# Spindle_Control.net
KiCad netlist of a schematic drawn in Altium Designer
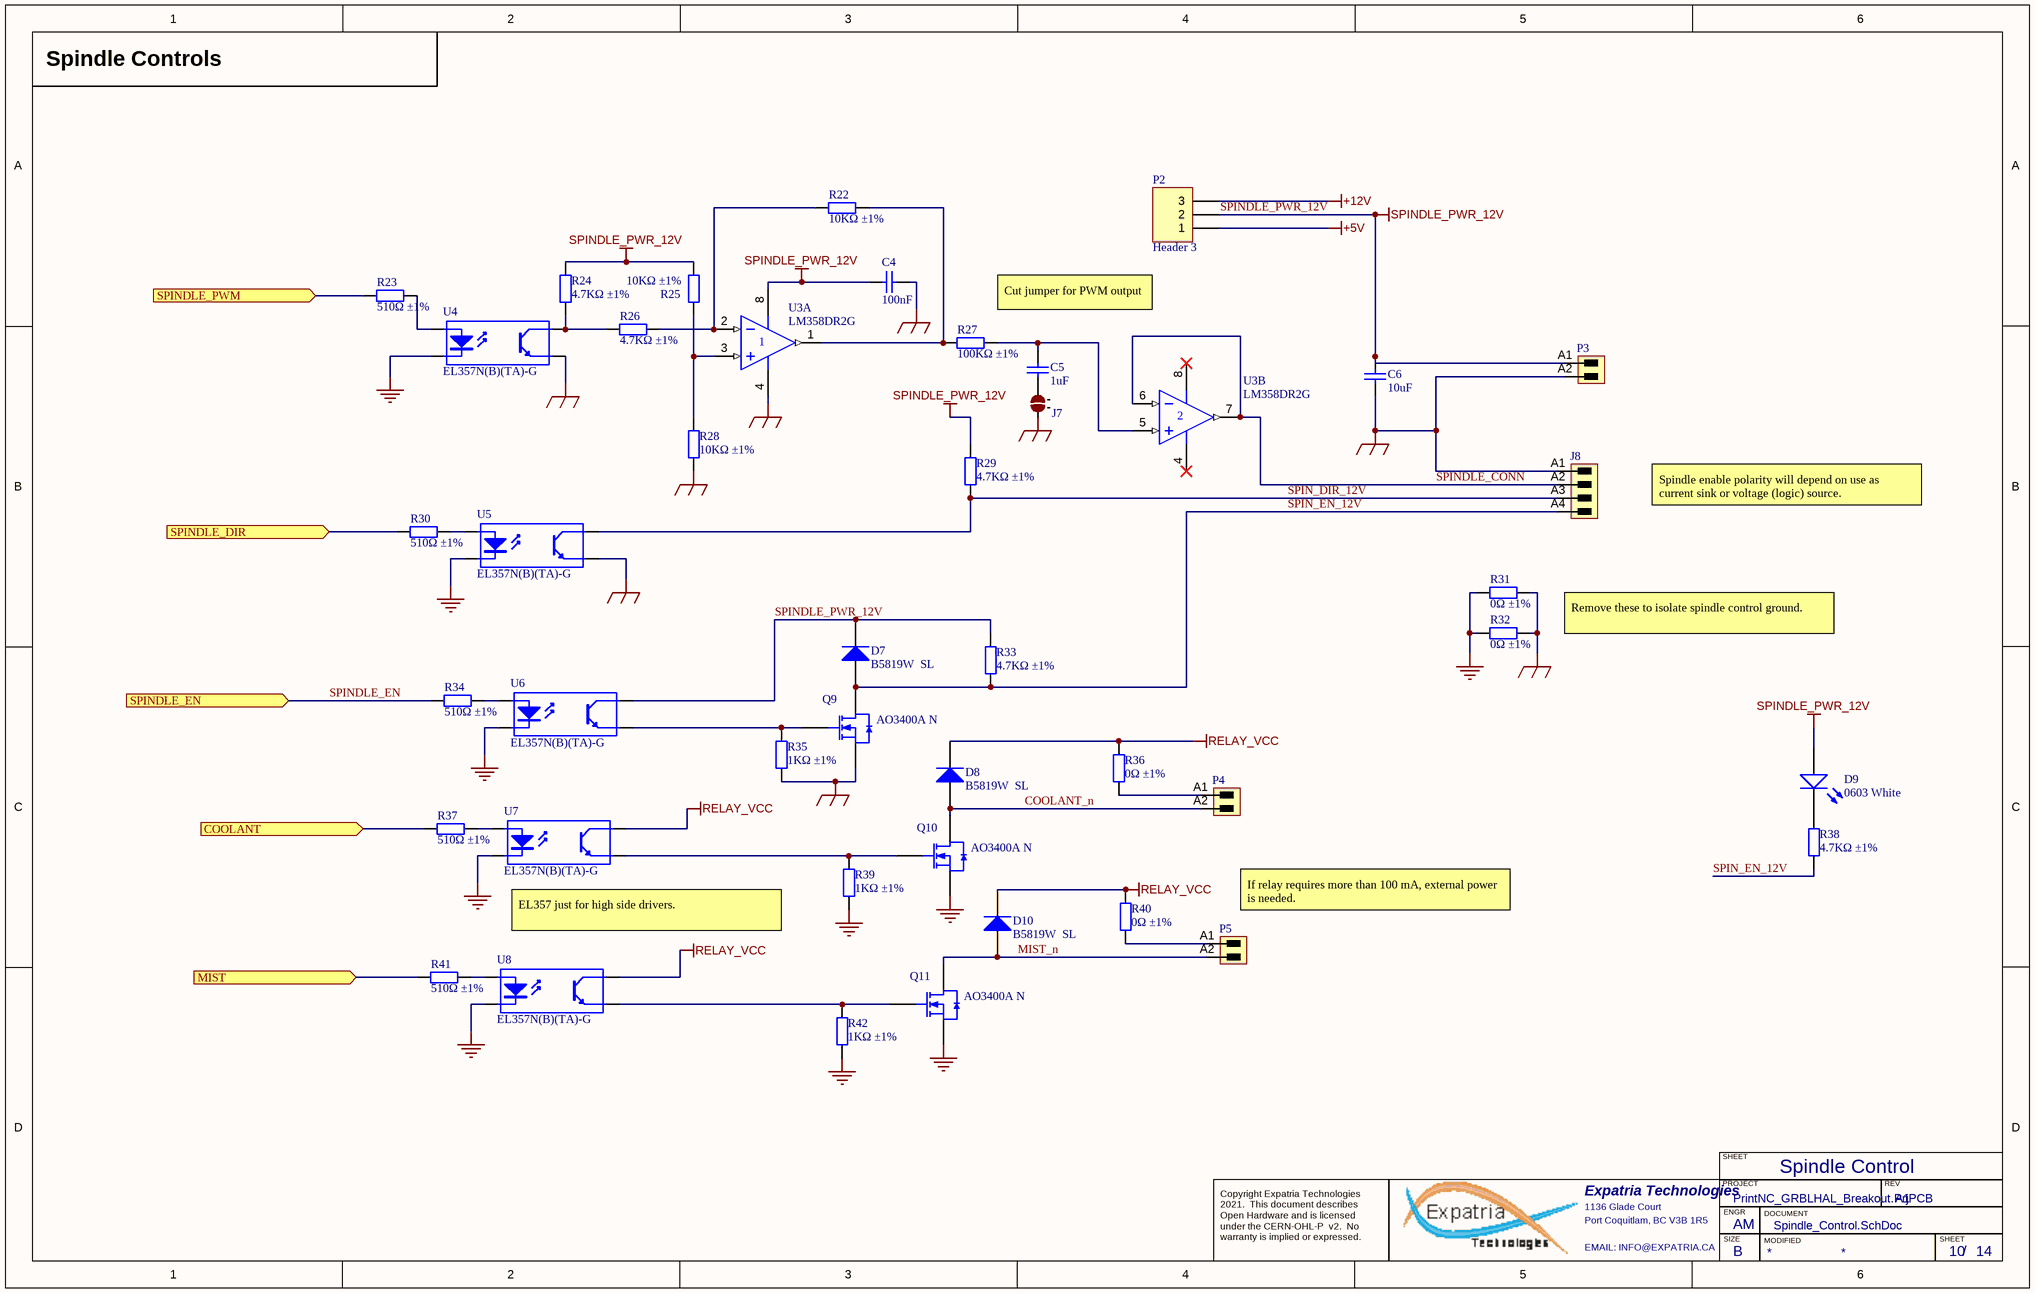
[diagram p0: Spindle_Control.SchDoc]

(export (version "E")
  (design (tool "Eeschema 10.0.6"))
  (components
    (comp (ref "C4")
      (value "100nF")
      (footprint "0603_C")
      (description "Chip capacitors")
      (fields (field (name "MANUFACTURER") "YAGEO") (field (name "PARTNUMBER") "CC0603KRX7R9BB104"))
      (libsource (lib "Cap") (part "0603 100nF (104) 10% 50V"))
    )
    (comp (ref "C5")
      (value "1uF")
      (footprint "0603_C")
      (description "Chip capacitors")
      (fields
        (field (name "MANUFACTURER") "Samsung Electro-Mechanics")
        (field (name "PARTNUMBER") "CL10A105KB8NNNC")
      )
      (libsource (lib "Cap") (part "0603 1uF (105) 10% 50V"))
    )
    (comp (ref "C6")
      (value "10uF")
      (footprint "1206_C")
      (description "Chip capacitors")
      (fields
        (field (name "MANUFACTURER") "Samsung Electro-Mechanics")
        (field (name "PARTNUMBER") "CL31A106KBHNNNE")
      )
      (libsource (lib "Cap") (part "1206 10uF (106) 10% 50V"))
    )
    (comp (ref "D7")
      (value "B5819W  SL")
      (footprint "SOD-123")
      (description "Schottky Diode")
      (libsource (lib "Diode") (part "SOD-123 B5819W  SL"))
    )
    (comp (ref "D8")
      (value "B5819W  SL")
      (footprint "SOD-123")
      (description "Schottky Diode")
      (libsource (lib "Diode") (part "SOD-123 B5819W  SL"))
    )
    (comp (ref "D9")
      (value "0603 White")
      (footprint "0603_LED_S1")
      (description "LED")
      (libsource (lib "LED") (part "0603 LED White"))
    )
    (comp (ref "D10")
      (value "B5819W  SL")
      (footprint "SOD-123")
      (description "Schottky Diode")
      (libsource (lib "Diode") (part "SOD-123 B5819W  SL"))
    )
    (comp (ref "J7")
      (value "2 way net solder junction - Normally Open")
      (footprint "2waySolder_NO")
      (libsource (lib "NetTieLib") (part "2waySolderNO"))
    )
    (comp (ref "J8")
      (value "~")
      (footprint "SL_SMT_3_5_180G_04")
      (description "OMNIMATE Signal - series BL/SL 3.50")
      (fields (field (name "PARTNUMBER") "1751264") (field (name "MANUFACTURER") "Phoenix Contact"))
      (libsource (lib "PrintNC_GRBLHAL_Breakout") (part "Header_Male_04_1x04"))
    )
    (comp (ref "P2")
      (value "Header 3")
      (footprint "HDR1X3")
      (description "Header, 3-Pin")
      (fields (field (name "PUBLISHER") "Altium Limited"))
      (libsource (lib "PrintNC_GRBLHAL_Breakout") (part "Header 3"))
    )
    (comp (ref "P3")
      (value "~")
      (footprint "SL_3_50_180G_02")
      (fields
        (field (name "PARTNUMBER") "WJ15EDGVC-3.5-2P")
        (field (name "MANUFACTURER") "Ningbo Kangnex Elec")
      )
      (libsource (lib "PrintNC_GRBLHAL_Breakout") (part "Header_Male_02_1x02"))
    )
    (comp (ref "P4")
      (value "~")
      (footprint "SL_3_50_180G_02")
      (fields
        (field (name "PARTNUMBER") "WJ15EDGVC-3.5-2P")
        (field (name "MANUFACTURER") "Ningbo Kangnex Elec")
      )
      (libsource (lib "PrintNC_GRBLHAL_Breakout") (part "Header_Male_02_1x02"))
    )
    (comp (ref "P5")
      (value "~")
      (footprint "SL_3_50_180G_02")
      (fields
        (field (name "PARTNUMBER") "WJ15EDGVC-3.5-2P")
        (field (name "MANUFACTURER") "Ningbo Kangnex Elec")
      )
      (libsource (lib "PrintNC_GRBLHAL_Breakout") (part "Header_Male_02_1x02"))
    )
    (comp (ref "Q9")
      (value "AO3400A N")
      (footprint "SOT-23-3L")
      (description "MOS(场效应管)")
      (libsource (lib "PrintNC_GRBLHAL_Breakout") (part "AO3400A N道沟 X0YV1T SOT-23"))
    )
    (comp (ref "Q10")
      (value "AO3400A N")
      (footprint "SOT-23-3L")
      (description "MOS(场效应管)")
      (libsource (lib "PrintNC_GRBLHAL_Breakout") (part "AO3400A N道沟 X0YV1T SOT-23"))
    )
    (comp (ref "Q11")
      (value "AO3400A N")
      (footprint "SOT-23-3L")
      (description "MOS(场效应管)")
      (libsource (lib "PrintNC_GRBLHAL_Breakout") (part "AO3400A N道沟 X0YV1T SOT-23"))
    )
    (comp (ref "R22")
      (value "10KΩ ±1%")
      (footprint "0402_R")
      (description "Chip resistor")
      (fields (field (name "MANUFACTURER") "Uniroyal Elec") (field (name "PARTNUMBER") "0402WGF1002TCE"))
      (libsource (lib "") (part "0402 10K (1002) 1%_1"))
    )
    (comp (ref "R23")
      (value "510Ω ±1%")
      (footprint "0402_R")
      (description "Chip resistor")
      (fields (field (name "MANUFACTURER") "Uniroyal Elec") (field (name "PARTNUMBER") "0402WGF5100TCE"))
      (libsource (lib "PrintNC_GRBLHAL_Breakout") (part "0402 510R (5100) 1%"))
    )
    (comp (ref "R24")
      (value "4.7KΩ ±1%")
      (footprint "0402_R")
      (description "Chip resistor")
      (fields (field (name "MANUFACTURER") "Uniroyal Elec") (field (name "PARTNUMBER") "0402WGF4701TCE"))
      (libsource (lib "") (part "0402 4.7K (4701) 1%_2"))
    )
    (comp (ref "R25")
      (value "10KΩ ±1%")
      (footprint "0402_R")
      (description "Chip resistor")
      (fields (field (name "MANUFACTURER") "Uniroyal Elec") (field (name "PARTNUMBER") "0402WGF1002TCE"))
      (libsource (lib "PrintNC_GRBLHAL_Breakout") (part "0402 10K (1002) 1%"))
    )
    (comp (ref "R26")
      (value "4.7KΩ ±1%")
      (footprint "0402_R")
      (description "Chip resistor")
      (fields (field (name "MANUFACTURER") "Uniroyal Elec") (field (name "PARTNUMBER") "0402WGF4701TCE"))
      (libsource (lib "") (part "0402 4.7K (4701) 1%_1"))
    )
    (comp (ref "R27")
      (value "100KΩ ±1%")
      (footprint "0402_R")
      (description "Chip resistor")
      (fields (field (name "MANUFACTURER") "Uniroyal Elec") (field (name "PARTNUMBER") "0402WGF1003TCE"))
      (libsource (lib "PrintNC_GRBLHAL_Breakout") (part "0402 100K (1003) 1%"))
    )
    (comp (ref "R28")
      (value "10KΩ ±1%")
      (footprint "0402_R")
      (description "Chip resistor")
      (fields (field (name "MANUFACTURER") "Uniroyal Elec") (field (name "PARTNUMBER") "0402WGF1002TCE"))
      (libsource (lib "PrintNC_GRBLHAL_Breakout") (part "0402 10K (1002) 1%"))
    )
    (comp (ref "R29")
      (value "4.7KΩ ±1%")
      (footprint "0402_R")
      (description "Chip resistor")
      (fields (field (name "MANUFACTURER") "Uniroyal Elec") (field (name "PARTNUMBER") "0402WGF4701TCE"))
      (libsource (lib "PrintNC_GRBLHAL_Breakout") (part "0402 4.7K (4701) 1%"))
    )
    (comp (ref "R30")
      (value "510Ω ±1%")
      (footprint "0402_R")
      (description "Chip resistor")
      (fields (field (name "MANUFACTURER") "Uniroyal Elec") (field (name "PARTNUMBER") "0402WGF5100TCE"))
      (libsource (lib "PrintNC_GRBLHAL_Breakout") (part "0402 510R (5100) 1%"))
    )
    (comp (ref "R31")
      (value "0Ω ±1%")
      (footprint "0402_R")
      (description "Chip resistor")
      (fields (field (name "POWER") "1/16W") (field (name "MANUFACTURER") "Uniroyal Elec"))
      (libsource (lib "PrintNC_GRBLHAL_Breakout") (part "0402 0R (0R0) 1%"))
    )
    (comp (ref "R32")
      (value "0Ω ±1%")
      (footprint "0402_R")
      (description "Chip resistor")
      (fields (field (name "POWER") "1/16W") (field (name "MANUFACTURER") "Uniroyal Elec"))
      (libsource (lib "PrintNC_GRBLHAL_Breakout") (part "0402 0R (0R0) 1%"))
    )
    (comp (ref "R33")
      (value "4.7KΩ ±1%")
      (footprint "0402_R")
      (description "Chip resistor")
      (fields (field (name "MANUFACTURER") "Uniroyal Elec") (field (name "PARTNUMBER") "0402WGF4701TCE"))
      (libsource (lib "PrintNC_GRBLHAL_Breakout") (part "0402 4.7K (4701) 1%"))
    )
    (comp (ref "R34")
      (value "510Ω ±1%")
      (footprint "0402_R")
      (description "Chip resistor")
      (fields (field (name "MANUFACTURER") "Uniroyal Elec") (field (name "PARTNUMBER") "0402WGF5100TCE"))
      (libsource (lib "PrintNC_GRBLHAL_Breakout") (part "0402 510R (5100) 1%"))
    )
    (comp (ref "R35")
      (value "1KΩ ±1%")
      (footprint "0402_R")
      (description "Chip resistor")
      (fields (field (name "MANUFACTURER") "Uniroyal Elec") (field (name "PARTNUMBER") "0402WGF1001TCE"))
      (libsource (lib "") (part "0402 1K (1001) 1%_1"))
    )
    (comp (ref "R36")
      (value "0Ω ±1%")
      (footprint "0402_R")
      (description "Chip resistor")
      (fields (field (name "MANUFACTURER") "Uniroyal Elec") (field (name "PARTNUMBER") "0402WGF0000TCE"))
      (libsource (lib "") (part "0402 0R (0R0) 1%_1"))
    )
    (comp (ref "R37")
      (value "510Ω ±1%")
      (footprint "0402_R")
      (description "Chip resistor")
      (fields (field (name "MANUFACTURER") "Uniroyal Elec") (field (name "PARTNUMBER") "0402WGF5100TCE"))
      (libsource (lib "PrintNC_GRBLHAL_Breakout") (part "0402 510R (5100) 1%"))
    )
    (comp (ref "R38")
      (value "4.7KΩ ±1%")
      (footprint "0402_R")
      (description "Chip resistor")
      (fields (field (name "MANUFACTURER") "Uniroyal Elec") (field (name "PARTNUMBER") "0402WGF4701TCE"))
      (libsource (lib "PrintNC_GRBLHAL_Breakout") (part "0402 4.7K (4701) 1%"))
    )
    (comp (ref "R39")
      (value "1KΩ ±1%")
      (footprint "0402_R")
      (description "Chip resistor")
      (fields (field (name "MANUFACTURER") "Uniroyal Elec") (field (name "PARTNUMBER") "0402WGF1001TCE"))
      (libsource (lib "PrintNC_GRBLHAL_Breakout") (part "0402 1K (1001) 1%"))
    )
    (comp (ref "R40")
      (value "0Ω ±1%")
      (footprint "0402_R")
      (description "Chip resistor")
      (fields (field (name "MANUFACTURER") "Uniroyal Elec") (field (name "PARTNUMBER") "0402WGF0000TCE"))
      (libsource (lib "") (part "0402 0R (0R0) 1%_1"))
    )
    (comp (ref "R41")
      (value "510Ω ±1%")
      (footprint "0402_R")
      (description "Chip resistor")
      (fields (field (name "MANUFACTURER") "Uniroyal Elec") (field (name "PARTNUMBER") "0402WGF5100TCE"))
      (libsource (lib "PrintNC_GRBLHAL_Breakout") (part "0402 510R (5100) 1%"))
    )
    (comp (ref "R42")
      (value "1KΩ ±1%")
      (footprint "0402_R")
      (description "Chip resistor")
      (fields (field (name "MANUFACTURER") "Uniroyal Elec") (field (name "PARTNUMBER") "0402WGF1001TCE"))
      (libsource (lib "PrintNC_GRBLHAL_Breakout") (part "0402 1K (1001) 1%"))
    )
    (comp (ref "U3")
      (value "LM358DR2G")
      (footprint "SOIC-8_150mil")
      (description "LM358DR2G,  Dual Op Amp,  5 - 28 V,  8-PinSOIC")
      (libsource (lib "PrintNC_GRBLHAL_Breakout") (part "LM358DR2G_[C7950]"))
    )
    (comp (ref "U4")
      (value "EL357N(B)(TA)-G")
      (footprint "SOP-4_P2.54")
      (description "Optocoupler SOP-4, EL357N(B)(TA)-G, Everlight Electronics")
      (libsource (lib "PrintNC_GRBLHAL_Breakout") (part "EL357N(B)(TA)-G_[C6649]"))
    )
    (comp (ref "U5")
      (value "EL357N(B)(TA)-G")
      (footprint "SOP-4_P2.54")
      (description "Optocoupler SOP-4, EL357N(B)(TA)-G, Everlight Electronics")
      (libsource (lib "PrintNC_GRBLHAL_Breakout") (part "EL357N(B)(TA)-G_[C6649]"))
    )
    (comp (ref "U6")
      (value "EL357N(B)(TA)-G")
      (footprint "SOP-4_P2.54")
      (description "Optocoupler SOP-4, EL357N(B)(TA)-G, Everlight Electronics")
      (libsource (lib "PrintNC_GRBLHAL_Breakout") (part "EL357N(B)(TA)-G_[C6649]"))
    )
    (comp (ref "U7")
      (value "EL357N(B)(TA)-G")
      (footprint "SOP-4_P2.54")
      (description "Optocoupler SOP-4, EL357N(B)(TA)-G, Everlight Electronics")
      (libsource (lib "PrintNC_GRBLHAL_Breakout") (part "EL357N(B)(TA)-G_[C6649]"))
    )
    (comp (ref "U8")
      (value "EL357N(B)(TA)-G")
      (footprint "SOP-4_P2.54")
      (description "Optocoupler SOP-4, EL357N(B)(TA)-G, Everlight Electronics")
      (libsource (lib "PrintNC_GRBLHAL_Breakout") (part "EL357N(B)(TA)-G_[C6649]"))
    )
  )
  (nets
    (net (code "1") (name "+5V") (class "Default")
      (node (ref "P2") (pin "1") (pinfunction "1_1") (pintype "passive"))
    )
    (net (code "2") (name "+12V") (class "Default")
      (node (ref "P2") (pin "3") (pinfunction "3_3") (pintype "passive"))
    )
    (net (code "3") (name "/COOLANT") (class "Default")
      (node (ref "R37") (pin "1") (pinfunction "1_1") (pintype "passive"))
    )
    (net (code "4") (name "/COOLANT_n") (class "Default")
      (node (ref "D8") (pin "1") (pinfunction "A_1") (pintype "passive"))
      (node (ref "P4") (pin "A2") (pinfunction "A2_A2") (pintype "passive"))
      (node (ref "Q10") (pin "3") (pinfunction "D_3") (pintype "passive"))
    )
    (net (code "5") (name "/MIST") (class "Default")
      (node (ref "R41") (pin "1") (pinfunction "1_1") (pintype "passive"))
    )
    (net (code "6") (name "/MIST_n") (class "Default")
      (node (ref "D10") (pin "1") (pinfunction "A_1") (pintype "passive"))
      (node (ref "P5") (pin "A2") (pinfunction "A2_A2") (pintype "passive"))
      (node (ref "Q11") (pin "3") (pinfunction "D_3") (pintype "passive"))
    )
    (net (code "7") (name "/SPINDLE_CONN") (class "Default")
      (node (ref "J8") (pin "A2") (pinfunction "A2_A2") (pintype "passive"))
      (node (ref "U3") (pin "6") (pinfunction "IN-_6") (pintype "input"))
      (node (ref "U3") (pin "7") (pinfunction "OUT_7") (pintype "output"))
    )
    (net (code "8") (name "/SPINDLE_DIR") (class "Default")
      (node (ref "R30") (pin "1") (pinfunction "1_1") (pintype "passive"))
    )
    (net (code "9") (name "/SPINDLE_EN") (class "Default")
      (node (ref "R34") (pin "1") (pinfunction "1_1") (pintype "passive"))
    )
    (net (code "10") (name "/SPINDLE_PWM") (class "Default")
      (node (ref "R23") (pin "1") (pinfunction "1_1") (pintype "passive"))
    )
    (net (code "11") (name "/SPIN_DIR_12V") (class "Default")
      (node (ref "J8") (pin "A3") (pinfunction "A3_A3") (pintype "passive"))
      (node (ref "R29") (pin "1") (pinfunction "1_1") (pintype "passive"))
      (node (ref "U5") (pin "4") (pinfunction "C_4") (pintype "passive"))
    )
    (net (code "12") (name "/SPIN_EN_12V") (class "Default")
      (node (ref "D7") (pin "1") (pinfunction "A_1") (pintype "passive"))
      (node (ref "J8") (pin "A4") (pinfunction "A4_A4") (pintype "passive"))
      (node (ref "Q9") (pin "3") (pinfunction "D_3") (pintype "passive"))
      (node (ref "R33") (pin "1") (pinfunction "1_1") (pintype "passive"))
      (node (ref "R38") (pin "1") (pinfunction "1_1") (pintype "passive"))
    )
    (net (code "13") (name "GND") (class "Default")
      (node (ref "Q10") (pin "2") (pinfunction "S_2") (pintype "passive"))
      (node (ref "Q11") (pin "2") (pinfunction "S_2") (pintype "passive"))
      (node (ref "R31") (pin "1") (pinfunction "1_1") (pintype "passive"))
      (node (ref "R32") (pin "1") (pinfunction "1_1") (pintype "passive"))
      (node (ref "R39") (pin "1") (pinfunction "1_1") (pintype "passive"))
      (node (ref "R42") (pin "1") (pinfunction "1_1") (pintype "passive"))
      (node (ref "U4") (pin "2") (pinfunction "K_2") (pintype "passive"))
      (node (ref "U5") (pin "2") (pinfunction "K_2") (pintype "passive"))
      (node (ref "U6") (pin "2") (pinfunction "K_2") (pintype "passive"))
      (node (ref "U7") (pin "2") (pinfunction "K_2") (pintype "passive"))
      (node (ref "U8") (pin "2") (pinfunction "K_2") (pintype "passive"))
    )
    (net (code "14") (name "Net-(C5-Pad1)") (class "Default")
      (node (ref "C5") (pin "1") (pinfunction "1_1") (pintype "passive"))
      (node (ref "J7") (pin "2") (pinfunction "2_2") (pintype "passive"))
    )
    (net (code "15") (name "Net-(D9-PadK)") (class "Default")
      (node (ref "D9") (pin "K") (pinfunction "K_K") (pintype "passive"))
      (node (ref "R38") (pin "2") (pinfunction "2_2") (pintype "passive"))
    )
    (net (code "16") (name "Net-(P4-PadA1)") (class "Default")
      (node (ref "P4") (pin "A1") (pinfunction "A1_A1") (pintype "passive"))
      (node (ref "R36") (pin "2") (pinfunction "2_2") (pintype "passive"))
    )
    (net (code "17") (name "Net-(P5-PadA1)") (class "Default")
      (node (ref "P5") (pin "A1") (pinfunction "A1_A1") (pintype "passive"))
      (node (ref "R40") (pin "2") (pinfunction "2_2") (pintype "passive"))
    )
    (net (code "18") (name "Net-(Q9-G)") (class "Default")
      (node (ref "Q9") (pin "1") (pinfunction "G_1") (pintype "passive"))
      (node (ref "R35") (pin "1") (pinfunction "1_1") (pintype "passive"))
      (node (ref "U6") (pin "3") (pinfunction "E_3") (pintype "passive"))
    )
    (net (code "19") (name "Net-(Q10-G)") (class "Default")
      (node (ref "Q10") (pin "1") (pinfunction "G_1") (pintype "passive"))
      (node (ref "R39") (pin "2") (pinfunction "2_2") (pintype "passive"))
      (node (ref "U7") (pin "3") (pinfunction "E_3") (pintype "passive"))
    )
    (net (code "20") (name "Net-(Q11-G)") (class "Default")
      (node (ref "Q11") (pin "1") (pinfunction "G_1") (pintype "passive"))
      (node (ref "R42") (pin "2") (pinfunction "2_2") (pintype "passive"))
      (node (ref "U8") (pin "3") (pinfunction "E_3") (pintype "passive"))
    )
    (net (code "21") (name "Net-(U3A-IN+)") (class "Default")
      (node (ref "R25") (pin "2") (pinfunction "2_2") (pintype "passive"))
      (node (ref "R28") (pin "1") (pinfunction "1_1") (pintype "passive"))
      (node (ref "U3") (pin "3") (pinfunction "IN+_3") (pintype "input"))
    )
    (net (code "22") (name "Net-(U3A-IN-)") (class "Default")
      (node (ref "R22") (pin "1") (pinfunction "1_1") (pintype "passive"))
      (node (ref "R26") (pin "2") (pinfunction "2_2") (pintype "passive"))
      (node (ref "U3") (pin "2") (pinfunction "IN-_2") (pintype "input"))
    )
    (net (code "23") (name "Net-(U3A-OUT)") (class "Default")
      (node (ref "R22") (pin "2") (pinfunction "2_2") (pintype "passive"))
      (node (ref "R27") (pin "2") (pinfunction "2_2") (pintype "passive"))
      (node (ref "U3") (pin "1") (pinfunction "OUT_1") (pintype "output"))
    )
    (net (code "24") (name "Net-(U3B-IN+)") (class "Default")
      (node (ref "C5") (pin "2") (pinfunction "2_2") (pintype "passive"))
      (node (ref "R27") (pin "1") (pinfunction "1_1") (pintype "passive"))
      (node (ref "U3") (pin "5") (pinfunction "IN+_5") (pintype "input"))
    )
    (net (code "25") (name "Net-(U4-A)") (class "Default")
      (node (ref "R23") (pin "2") (pinfunction "2_2") (pintype "passive"))
      (node (ref "U4") (pin "1") (pinfunction "A_1") (pintype "passive"))
    )
    (net (code "26") (name "Net-(U4-C)") (class "Default")
      (node (ref "R24") (pin "2") (pinfunction "2_2") (pintype "passive"))
      (node (ref "R26") (pin "1") (pinfunction "1_1") (pintype "passive"))
      (node (ref "U4") (pin "4") (pinfunction "C_4") (pintype "passive"))
    )
    (net (code "27") (name "Net-(U5-A)") (class "Default")
      (node (ref "R30") (pin "2") (pinfunction "2_2") (pintype "passive"))
      (node (ref "U5") (pin "1") (pinfunction "A_1") (pintype "passive"))
    )
    (net (code "28") (name "Net-(U6-A)") (class "Default")
      (node (ref "R34") (pin "2") (pinfunction "2_2") (pintype "passive"))
      (node (ref "U6") (pin "1") (pinfunction "A_1") (pintype "passive"))
    )
    (net (code "29") (name "Net-(U7-A)") (class "Default")
      (node (ref "R37") (pin "2") (pinfunction "2_2") (pintype "passive"))
      (node (ref "U7") (pin "1") (pinfunction "A_1") (pintype "passive"))
    )
    (net (code "30") (name "Net-(U8-A)") (class "Default")
      (node (ref "R41") (pin "2") (pinfunction "2_2") (pintype "passive"))
      (node (ref "U8") (pin "1") (pinfunction "A_1") (pintype "passive"))
    )
    (net (code "31") (name "RELAY_VCC") (class "Default")
      (node (ref "D10") (pin "2") (pinfunction "K_2") (pintype "passive"))
      (node (ref "D8") (pin "2") (pinfunction "K_2") (pintype "passive"))
      (node (ref "R36") (pin "1") (pinfunction "1_1") (pintype "passive"))
      (node (ref "R40") (pin "1") (pinfunction "1_1") (pintype "passive"))
      (node (ref "U7") (pin "4") (pinfunction "C_4") (pintype "passive"))
      (node (ref "U8") (pin "4") (pinfunction "C_4") (pintype "passive"))
    )
    (net (code "32") (name "SPINDLE_PWR_12V") (class "Default")
      (node (ref "C4") (pin "2") (pinfunction "2_2") (pintype "passive"))
      (node (ref "C6") (pin "2") (pinfunction "2_2") (pintype "passive"))
      (node (ref "D7") (pin "2") (pinfunction "K_2") (pintype "passive"))
      (node (ref "D9") (pin "A") (pinfunction "A_A") (pintype "passive"))
      (node (ref "P2") (pin "2") (pinfunction "2_2") (pintype "passive"))
      (node (ref "P3") (pin "A1") (pinfunction "A1_A1") (pintype "passive"))
      (node (ref "R24") (pin "1") (pinfunction "1_1") (pintype "passive"))
      (node (ref "R25") (pin "1") (pinfunction "1_1") (pintype "passive"))
      (node (ref "R29") (pin "2") (pinfunction "2_2") (pintype "passive"))
      (node (ref "R33") (pin "2") (pinfunction "2_2") (pintype "passive"))
      (node (ref "U3") (pin "8") (pinfunction "V+_8") (pintype "power_in"))
      (node (ref "U6") (pin "4") (pinfunction "C_4") (pintype "passive"))
    )
    (net (code "33") (name "SPIN_GND") (class "Default")
      (node (ref "C4") (pin "1") (pinfunction "1_1") (pintype "passive"))
      (node (ref "C6") (pin "1") (pinfunction "1_1") (pintype "passive"))
      (node (ref "J7") (pin "1") (pinfunction "1_1") (pintype "passive"))
      (node (ref "J8") (pin "A1") (pinfunction "A1_A1") (pintype "passive"))
      (node (ref "P3") (pin "A2") (pinfunction "A2_A2") (pintype "passive"))
      (node (ref "Q9") (pin "2") (pinfunction "S_2") (pintype "passive"))
      (node (ref "R28") (pin "2") (pinfunction "2_2") (pintype "passive"))
      (node (ref "R31") (pin "2") (pinfunction "2_2") (pintype "passive"))
      (node (ref "R32") (pin "2") (pinfunction "2_2") (pintype "passive"))
      (node (ref "R35") (pin "2") (pinfunction "2_2") (pintype "passive"))
      (node (ref "U3") (pin "4") (pinfunction "V-_4") (pintype "power_in"))
      (node (ref "U4") (pin "3") (pinfunction "E_3") (pintype "passive"))
      (node (ref "U5") (pin "3") (pinfunction "E_3") (pintype "passive"))
    )
    (net (code "34") (name "unconnected-(U3B-V+-Pad8)") (class "Default")
      (node (ref "U3") (pin "8") (pinfunction "V+_8") (pintype "power_in+no_connect"))
    )
    (net (code "35") (name "unconnected-(U3B-V--Pad4)") (class "Default")
      (node (ref "U3") (pin "4") (pinfunction "V-_4") (pintype "power_in+no_connect"))
    )
  )
)
